# Controller.net
KiCad netlist of a schematic drawn in Altium Designer
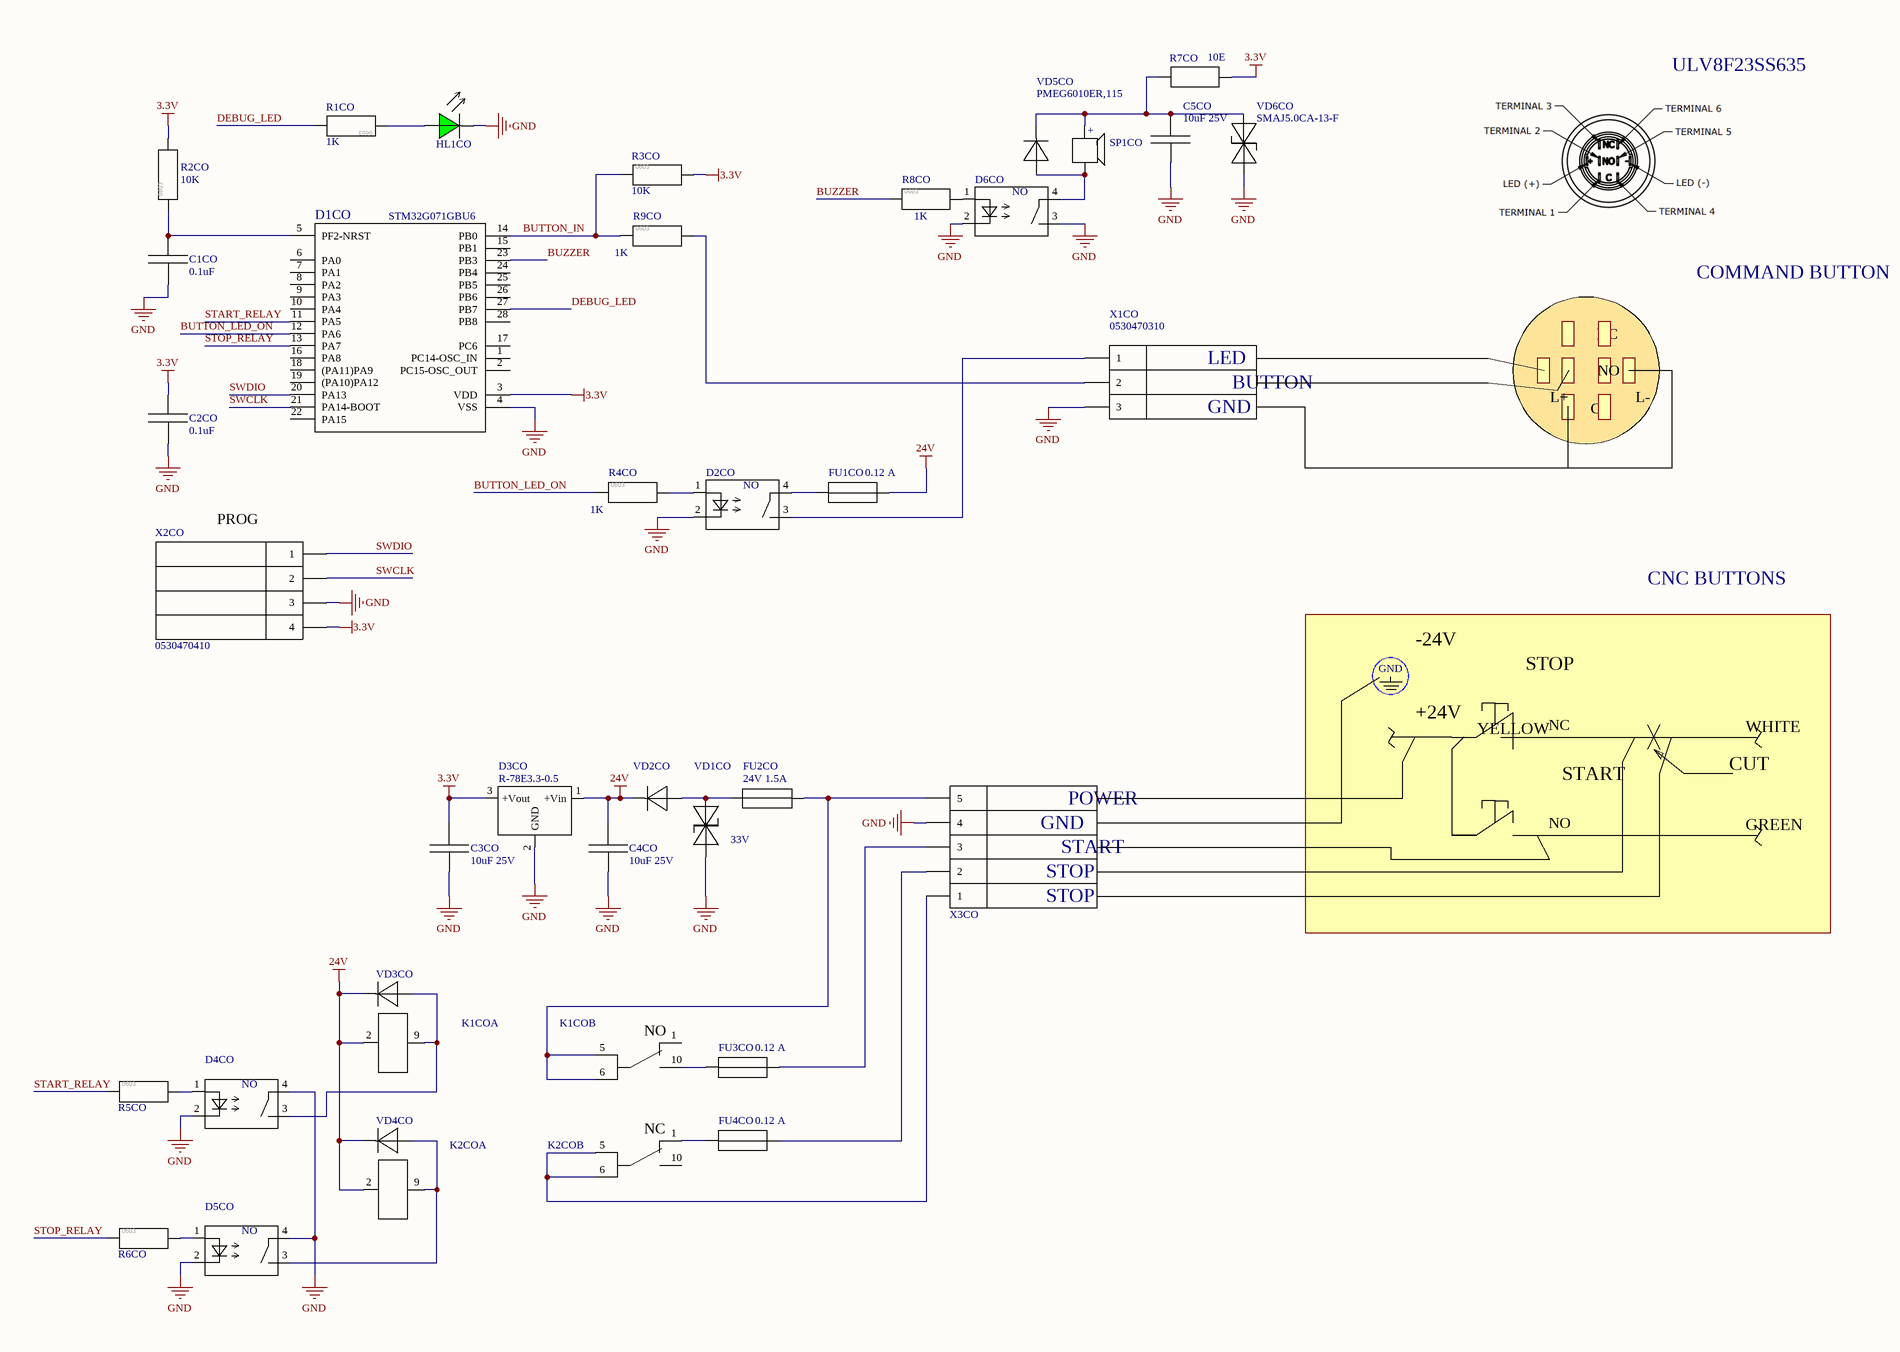
[diagram p0: Controller.SchDoc, left]
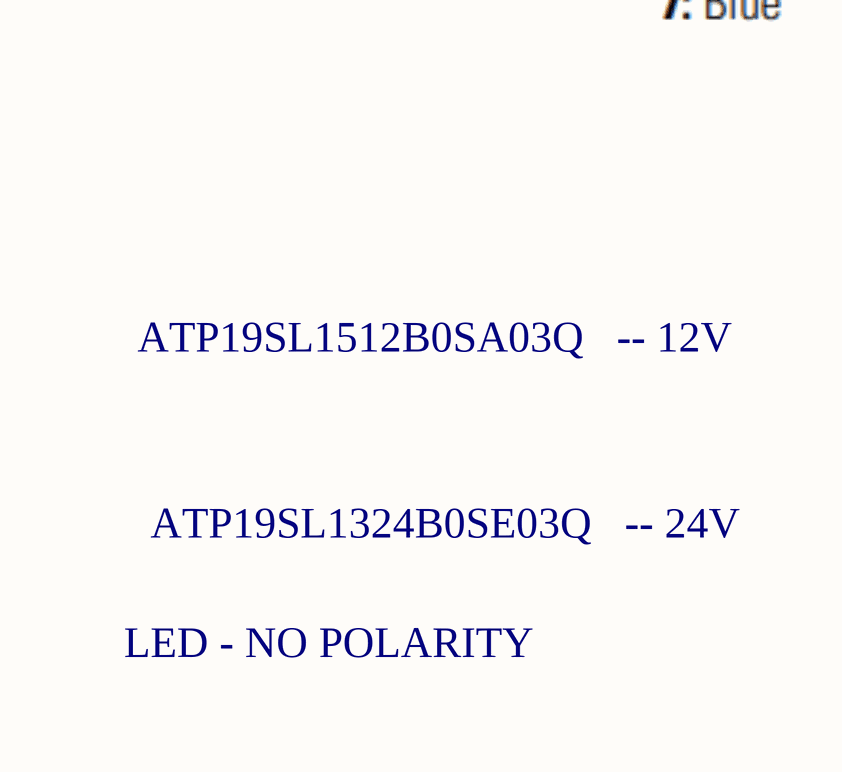
[diagram p1: Controller.SchDoc, right]

(export (version "E")
  (design (tool "Eeschema 10.0.6"))
  (components
    (comp (ref "C1CO")
      (value "0.1uF")
      (footprint "C0603pads")
      (description "CAP CER 0.1UF 50V X7R 0603 jlc")
      (fields
        (field (name "MANUFACTURER") "Samsung Electro-Mechanics")
        (field (name "PART NUMBER") "CL10B104KB8NNNC")
        (field (name "PUBLISHER") "*")
      )
      (libsource (lib "MC2") (part "CL10B104KB8NNNC"))
    )
    (comp (ref "C2CO")
      (value "0.1uF")
      (footprint "C0603pads")
      (description "CAP CER 0.1UF 50V X7R 0603 jlc")
      (fields
        (field (name "MANUFACTURER") "Samsung Electro-Mechanics")
        (field (name "PART NUMBER") "CL10B104KB8NNNC")
        (field (name "PUBLISHER") "*")
      )
      (libsource (lib "MC2") (part "CL10B104KB8NNNC"))
    )
    (comp (ref "C3CO")
      (value "10uF 25V")
      (footprint "C1210 LowESR")
      (description "CAP CER 10UF 25V X8R 1210")
      (fields
        (field (name "PART NUMBER") "C3225X8R1E106K250AC")
        (field (name "MANUFACTURER") "TDK Corporation")
        (field (name "PUBLISHER") "*")
      )
      (libsource (lib "MC2") (part "C3225X8R1E106K250AC"))
    )
    (comp (ref "C4CO")
      (value "10uF 25V")
      (footprint "C1210 LowESR")
      (description "CAP CER 10UF 25V X8R 1210")
      (fields
        (field (name "PART NUMBER") "C3225X8R1E106K250AC")
        (field (name "MANUFACTURER") "TDK Corporation")
        (field (name "PUBLISHER") "*")
      )
      (libsource (lib "MC2") (part "C3225X8R1E106K250AC"))
    )
    (comp (ref "C5CO")
      (value "10uF 25V")
      (footprint "C1210 LowESR")
      (description "CAP CER 10UF 25V X8R 1210")
      (fields
        (field (name "PART NUMBER") "C3225X8R1E106K250AC")
        (field (name "MANUFACTURER") "TDK Corporation")
        (field (name "PUBLISHER") "*")
      )
      (libsource (lib "MC2") (part "C3225X8R1E106K250AC"))
    )
    (comp (ref "D1CO")
      (value "STM32G071GBU6")
      (footprint "UFQFPN28")
      (description "IC MCU 32BIT 128KB FLSH 28UFQFPN jlc")
      (fields (field (name "MANUFACTURER") "STMicroelectronics"))
      (libsource (lib "MC2") (part "STM32G071GBU6"))
    )
    (comp (ref "D2CO")
      (value "CPC1014NTR")
      (footprint "SOP-4")
      (description "SSR RELAY SPST-NO 400MA 0-60V jlc")
      (fields (field (name "MANUFACTURER") "Littelfuse Inc.") (field (name "PUBLISHER") "*"))
      (libsource (lib "MC2") (part "CPC1014NTR"))
    )
    (comp (ref "D3CO")
      (value "R-78E3.3-0.5")
      (footprint "R-78XX-0.5")
      (description "DC DC CONVERTER 3.3V 2W")
      (fields (field (name "MANUFACTURER") "Recom Power"))
      (libsource (lib "MC2") (part "R-78E3.3-0.5"))
    )
    (comp (ref "D4CO")
      (value "CPC1014NTR")
      (footprint "SOP-4")
      (description "SSR RELAY SPST-NO 400MA 0-60V jlc")
      (fields (field (name "MANUFACTURER") "Littelfuse Inc.") (field (name "PUBLISHER") "*"))
      (libsource (lib "MC2") (part "CPC1014NTR"))
    )
    (comp (ref "D5CO")
      (value "CPC1014NTR")
      (footprint "SOP-4")
      (description "SSR RELAY SPST-NO 400MA 0-60V jlc")
      (fields (field (name "MANUFACTURER") "Littelfuse Inc.") (field (name "PUBLISHER") "*"))
      (libsource (lib "MC2") (part "CPC1014NTR"))
    )
    (comp (ref "D6CO")
      (value "CPC1014NTR")
      (footprint "SOP-4")
      (description "SSR RELAY SPST-NO 400MA 0-60V jlc")
      (fields (field (name "MANUFACTURER") "Littelfuse Inc.") (field (name "PUBLISHER") "*"))
      (libsource (lib "MC2") (part "CPC1014NTR"))
    )
    (comp (ref "FU1CO")
      (value "0.12 A")
      (footprint "MC:FUSE 1206")
      (description "PTC RESET FUSE 48V 120MA 1206 jlc")
      (fields
        (field (name "PART NUMBER") "0ZCJ0012FF2E")
        (field (name "MANUFACTURER") "Bel Fuse Inc.")
        (field (name "PUBLISHER") "*")
      )
      (libsource (lib "MC2") (part "0ZCJ0012FF2E"))
    )
    (comp (ref "FU2CO")
      (value "24V 1.5A")
      (footprint "MC2:FUSE 1812")
      (description "PTC RESET FUSE 24V 1.5A 1812 jlc")
      (fields
        (field (name "MANUFACTURER") "Littelfuse Inc.")
        (field (name "PART NUMBER") "1812L150/24MR")
        (field (name "PUBLISHER") "*")
      )
      (libsource (lib "MC2") (part "1812L150/24MR"))
    )
    (comp (ref "FU3CO")
      (value "0.12 A")
      (footprint "MC:FUSE 1206")
      (description "PTC RESET FUSE 48V 120MA 1206 jlc")
      (fields
        (field (name "PART NUMBER") "0ZCJ0012FF2E")
        (field (name "MANUFACTURER") "Bel Fuse Inc.")
        (field (name "PUBLISHER") "*")
      )
      (libsource (lib "MC2") (part "0ZCJ0012FF2E"))
    )
    (comp (ref "FU4CO")
      (value "0.12 A")
      (footprint "MC:FUSE 1206")
      (description "PTC RESET FUSE 48V 120MA 1206 jlc")
      (fields
        (field (name "PART NUMBER") "0ZCJ0012FF2E")
        (field (name "MANUFACTURER") "Bel Fuse Inc.")
        (field (name "PUBLISHER") "*")
      )
      (libsource (lib "MC2") (part "0ZCJ0012FF2E"))
    )
    (comp (ref "HL1CO")
      (value "KT-0805G")
      (footprint "MC2:LED 0805 GREEN")
      (description "LED EMERALD GREEN 0805 SMD jlc")
      (fields (field (name "MANUFACTURER") "Hubei KENTO Elec") (field (name "PUBLISHER") "*"))
      (libsource (lib "MC2") (part "KT-0805G"))
    )
    (comp (ref "K1CO")
      (value "G5V-1-DC24")
      (footprint "MC2:G5V-1")
      (description "RELAY GEN PURPOSE SPDT 1A 24VDC")
      (fields (field (name "MANUFACTURER") "Omron") (field (name "PUBLISHER") "*"))
      (libsource (lib "MC2") (part "G5V-1-DC24"))
    )
    (comp (ref "K2CO")
      (value "G5V-1-DC24")
      (footprint "MC2:G5V-1")
      (description "RELAY GEN PURPOSE SPDT 1A 24VDC")
      (fields (field (name "MANUFACTURER") "Omron") (field (name "PUBLISHER") "*"))
      (libsource (lib "MC2") (part "G5V-1-DC24"))
    )
    (comp (ref "R1CO")
      (value "1K")
      (footprint "R0603_MIN_pads")
      (description "RES SMD 1K OHM 1% 1/10W 0603 jlc")
      (fields
        (field (name "MANUFACTURER") "Yageo")
        (field (name "PART NUMBER") "RC0603FR-071KL")
        (field (name "PUBLISHER") "*")
      )
      (libsource (lib "MC2") (part "RC0603FR-071KL"))
    )
    (comp (ref "R2CO")
      (value "10K")
      (footprint "R0603_pads")
      (description "RES 10K OHM 1% 1/10W 0603 jlc")
      (fields
        (field (name "MANUFACTURER") "Yageo")
        (field (name "PART NUMBER") "RC0603FR-0710KL")
        (field (name "PUBLISHER") "*")
      )
      (libsource (lib "MC2") (part "RC0603FR-0710KL"))
    )
    (comp (ref "R3CO")
      (value "10K")
      (footprint "R0603_pads")
      (description "RES 10K OHM 1% 1/10W 0603 jlc")
      (fields
        (field (name "MANUFACTURER") "Yageo")
        (field (name "PART NUMBER") "RC0603FR-0710KL")
        (field (name "PUBLISHER") "*")
      )
      (libsource (lib "MC2") (part "RC0603FR-0710KL"))
    )
    (comp (ref "R4CO")
      (value "1K")
      (footprint "R0603_MIN_pads")
      (description "RES SMD 1K OHM 1% 1/10W 0603 jlc")
      (fields
        (field (name "MANUFACTURER") "Yageo")
        (field (name "PART NUMBER") "RC0603FR-071KL")
        (field (name "PUBLISHER") "*")
      )
      (libsource (lib "MC2") (part "RC0603FR-071KL"))
    )
    (comp (ref "R5CO")
      (value "RC0603FR-071KL")
      (footprint "R0603_MIN_pads")
      (description "RES SMD 1K OHM 1% 1/10W 0603 jlc")
      (fields (field (name "MANUFACTURER") "Yageo") (field (name "PUBLISHER") "*"))
      (libsource (lib "MC2") (part "RC0603FR-071KL"))
    )
    (comp (ref "R6CO")
      (value "RC0603FR-071KL")
      (footprint "R0603_MIN_pads")
      (description "RES SMD 1K OHM 1% 1/10W 0603 jlc")
      (fields (field (name "MANUFACTURER") "Yageo") (field (name "PUBLISHER") "*"))
      (libsource (lib "MC2") (part "RC0603FR-071KL"))
    )
    (comp (ref "R7CO")
      (value "10E")
      (footprint "MC2:R0805")
      (description "RES 10 OHM 1% 1/8W 0805 jlc")
      (fields
        (field (name "MANUFACTURER") "Yageo")
        (field (name "PART NUMBER") "RC0805FR-0710RL")
        (field (name "PUBLISHER") "*")
      )
      (libsource (lib "MC2") (part "RC0805FR-0710RL"))
    )
    (comp (ref "R8CO")
      (value "1K")
      (footprint "R0603_MIN_pads")
      (description "RES SMD 1K OHM 1% 1/10W 0603 jlc")
      (fields
        (field (name "MANUFACTURER") "Yageo")
        (field (name "PART NUMBER") "RC0603FR-071KL")
        (field (name "PUBLISHER") "*")
      )
      (libsource (lib "MC2") (part "RC0603FR-071KL"))
    )
    (comp (ref "R9CO")
      (value "1K")
      (footprint "R0603_MIN_pads")
      (description "RES SMD 1K OHM 1% 1/10W 0603 jlc")
      (fields
        (field (name "MANUFACTURER") "Yageo")
        (field (name "PART NUMBER") "RC0603FR-071KL")
        (field (name "PUBLISHER") "*")
      )
      (libsource (lib "MC2") (part "RC0603FR-071KL"))
    )
    (comp (ref "SP1CO")
      (value "MLT-9650")
      (footprint "buzer_9.6x9.6")
      (description "85dB Active (Built-in Driver Circuit) Electromagnetic Type 2.7kHz Buzzers ROHS jlc")
      (fields (field (name "MANUFACTURER") "Yageo") (field (name "PUBLISHER") "*"))
      (libsource (lib "MC2") (part "MLT-9650"))
    )
    (comp (ref "VD1CO")
      (value "33V")
      (footprint "MC2:SMAJ")
      (description "TVS DIODE 30VWM 64.3VC SMA")
      (fields
        (field (name "MANUFACTURER") "STMicroelectronics")
        (field (name "PART NUMBER") "SMAJ30CA-TR")
        (field (name "PUBLISHER") "*")
      )
      (libsource (lib "MC2") (part "SMAJ30CA-TR"))
    )
    (comp (ref "VD2CO")
      (value "PMEG6010ER,115")
      (footprint "SOD123")
      (description "DIODE SCHOTTKY 60V 1A SOD123W")
      (fields (field (name "MANUFACTURER") "Nexperia USA Inc.") (field (name "PUBLISHER") "*"))
      (libsource (lib "MC2") (part "PMEG6010ER,115"))
    )
    (comp (ref "VD3CO")
      (value "PMEG6010ER,115")
      (footprint "SOD123")
      (description "DIODE SCHOTTKY 60V 1A SOD123W")
      (fields (field (name "MANUFACTURER") "Nexperia USA Inc.") (field (name "PUBLISHER") "*"))
      (libsource (lib "MC2") (part "PMEG6010ER,115"))
    )
    (comp (ref "VD4CO")
      (value "PMEG6010ER,115")
      (footprint "SOD123")
      (description "DIODE SCHOTTKY 60V 1A SOD123W")
      (fields (field (name "MANUFACTURER") "Nexperia USA Inc.") (field (name "PUBLISHER") "*"))
      (libsource (lib "MC2") (part "PMEG6010ER,115"))
    )
    (comp (ref "VD5CO")
      (value "PMEG6010ER,115")
      (footprint "SOD123")
      (description "DIODE SCHOTTKY 60V 1A SOD123W")
      (fields
        (field (name "MANUFACTURER") "Nexperia USA Inc.")
        (field (name "PART NUMBER") "PMEG6010ER,115")
        (field (name "PUBLISHER") "*")
      )
      (libsource (lib "MC2") (part "PMEG6010ER,115"))
    )
    (comp (ref "VD6CO")
      (value "SMAJ5.0CA-13-F")
      (footprint "MC2:SMAJ")
      (description "TVS DIODE 5VWM 9.2VC SMA jlc")
      (fields (field (name "MANUFACTURER") "Diodes Incorporated") (field (name "PUBLISHER") "*"))
      (libsource (lib "MC2") (part "SMAJ5.0CA-13-F"))
    )
    (comp (ref "X1CO")
      (value "0530470310")
      (footprint "0530470310")
      (description "CONN HEADER VERT 3POS 1.25MM jlc")
      (fields (field (name "MANUFACTURER") "Molex") (field (name "PUBLISHER") "*"))
      (libsource (lib "MC2") (part "0530470310"))
    )
    (comp (ref "X2CO")
      (value "0530470410")
      (footprint "0530470410")
      (description "CONN HEADER VERT 4POS 1.25MM")
      (fields (field (name "MANUFACTURER") "Molex") (field (name "PUBLISHER") "*"))
      (libsource (lib "MC2") (part "0530470410"))
    )
    (comp (ref "X3CO")
      (value "1984992")
      (footprint "1984992")
      (description "TERM BLOCK 5POS 45DEG 3.5MM PCB")
      (fields (field (name "MANUFACTURER") "Phoenix Contact") (field (name "PUBLISHER") "*"))
      (libsource (lib "MC2") (part "1984992"))
    )
  )
  (nets
    (net (code "1") (name "/BUTTON_IN") (class "Default")
      (node (ref "D1CO") (pin "14") (pinfunction "PB0_14") (pintype "passive"))
      (node (ref "R3CO") (pin "1") (pinfunction "1_1") (pintype "passive"))
      (node (ref "R9CO") (pin "1") (pinfunction "1_1") (pintype "passive"))
    )
    (net (code "2") (name "/BUTTON_LED_ON") (class "Default")
      (node (ref "D1CO") (pin "12") (pinfunction "PA6_12") (pintype "passive"))
      (node (ref "R4CO") (pin "1") (pinfunction "1_1") (pintype "passive"))
    )
    (net (code "3") (name "/BUZZER") (class "Default")
      (node (ref "D1CO") (pin "23") (pinfunction "PB3_23") (pintype "passive"))
      (node (ref "R8CO") (pin "1") (pinfunction "1_1") (pintype "passive"))
    )
    (net (code "4") (name "/DEBUG_LED") (class "Default")
      (node (ref "D1CO") (pin "27") (pinfunction "PB7_27") (pintype "passive"))
      (node (ref "R1CO") (pin "2") (pinfunction "2_2") (pintype "passive"))
    )
    (net (code "5") (name "/START_RELAY") (class "Default")
      (node (ref "D1CO") (pin "11") (pinfunction "PA5_11") (pintype "passive"))
      (node (ref "R5CO") (pin "1") (pinfunction "1_1") (pintype "passive"))
    )
    (net (code "6") (name "/STOP_RELAY") (class "Default")
      (node (ref "D1CO") (pin "13") (pinfunction "PA7_13") (pintype "passive"))
      (node (ref "R6CO") (pin "1") (pinfunction "1_1") (pintype "passive"))
    )
    (net (code "7") (name "/SWCLK") (class "Default")
      (node (ref "D1CO") (pin "21") (pinfunction "PA14-BOOT_21") (pintype "passive"))
      (node (ref "X2CO") (pin "2") (pinfunction "2_2") (pintype "passive"))
    )
    (net (code "8") (name "/SWDIO") (class "Default")
      (node (ref "D1CO") (pin "20") (pinfunction "PA13_20") (pintype "passive"))
      (node (ref "X2CO") (pin "1") (pinfunction "1_1") (pintype "passive"))
    )
    (net (code "9") (name "3.3V") (class "Default")
      (node (ref "C2CO") (pin "1") (pinfunction "1_1") (pintype "passive"))
      (node (ref "C3CO") (pin "2") (pinfunction "2_2") (pintype "passive"))
      (node (ref "D1CO") (pin "3") (pinfunction "VDD_3") (pintype "power_in"))
      (node (ref "D3CO") (pin "3") (pinfunction "+Vout_3") (pintype "passive"))
      (node (ref "R2CO") (pin "2") (pinfunction "2_2") (pintype "passive"))
      (node (ref "R3CO") (pin "2") (pinfunction "2_2") (pintype "passive"))
      (node (ref "R7CO") (pin "2") (pinfunction "2_2") (pintype "passive"))
      (node (ref "X2CO") (pin "4") (pinfunction "4_4") (pintype "passive"))
    )
    (net (code "10") (name "24V") (class "Default")
      (node (ref "C4CO") (pin "2") (pinfunction "2_2") (pintype "passive"))
      (node (ref "D3CO") (pin "1") (pinfunction "+Vin_1") (pintype "passive"))
      (node (ref "FU1CO") (pin "2") (pinfunction "2_2") (pintype "passive"))
      (node (ref "K1CO") (pin "2") (pinfunction "2_2") (pintype "passive"))
      (node (ref "K2CO") (pin "2") (pinfunction "2_2") (pintype "passive"))
      (node (ref "VD2CO") (pin "1") (pinfunction "1_1") (pintype "passive"))
      (node (ref "VD3CO") (pin "1") (pinfunction "1_1") (pintype "passive"))
      (node (ref "VD4CO") (pin "1") (pinfunction "1_1") (pintype "passive"))
    )
    (net (code "11") (name "GND") (class "Default")
      (node (ref "C1CO") (pin "2") (pinfunction "2_2") (pintype "passive"))
      (node (ref "C2CO") (pin "2") (pinfunction "2_2") (pintype "passive"))
      (node (ref "C3CO") (pin "1") (pinfunction "1_1") (pintype "passive"))
      (node (ref "C4CO") (pin "1") (pinfunction "1_1") (pintype "passive"))
      (node (ref "C5CO") (pin "1") (pinfunction "1_1") (pintype "passive"))
      (node (ref "D1CO") (pin "4") (pinfunction "VSS_4") (pintype "power_in"))
      (node (ref "D2CO") (pin "2") (pinfunction "2_2") (pintype "passive"))
      (node (ref "D3CO") (pin "2") (pinfunction "GND_2") (pintype "passive"))
      (node (ref "D4CO") (pin "2") (pinfunction "2_2") (pintype "passive"))
      (node (ref "D4CO") (pin "4") (pinfunction "4_4") (pintype "passive"))
      (node (ref "D5CO") (pin "2") (pinfunction "2_2") (pintype "passive"))
      (node (ref "D5CO") (pin "4") (pinfunction "4_4") (pintype "passive"))
      (node (ref "D6CO") (pin "2") (pinfunction "2_2") (pintype "passive"))
      (node (ref "D6CO") (pin "3") (pinfunction "3_3") (pintype "passive"))
      (node (ref "HL1CO") (pin "2") (pinfunction "2_2") (pintype "passive"))
      (node (ref "VD1CO") (pin "1") (pinfunction "1_1") (pintype "passive"))
      (node (ref "VD6CO") (pin "1") (pinfunction "1_1") (pintype "passive"))
      (node (ref "X1CO") (pin "3") (pinfunction "3_3") (pintype "passive"))
      (node (ref "X2CO") (pin "3") (pinfunction "3_3") (pintype "passive"))
      (node (ref "X3CO") (pin "4") (pinfunction "4_4") (pintype "passive"))
    )
    (net (code "12") (name "Net-(C5CO-Pad2)") (class "Default")
      (node (ref "C5CO") (pin "2") (pinfunction "2_2") (pintype "passive"))
      (node (ref "R7CO") (pin "1") (pinfunction "1_1") (pintype "passive"))
      (node (ref "SP1CO") (pin "1") (pinfunction "1_1") (pintype "passive"))
      (node (ref "VD5CO") (pin "1") (pinfunction "1_1") (pintype "passive"))
      (node (ref "VD6CO") (pin "2") (pinfunction "2_2") (pintype "passive"))
    )
    (net (code "13") (name "Net-(D1CO-PF2-NRST)") (class "Default")
      (node (ref "C1CO") (pin "1") (pinfunction "1_1") (pintype "passive"))
      (node (ref "D1CO") (pin "5") (pinfunction "PF2-NRST_5") (pintype "passive"))
      (node (ref "R2CO") (pin "1") (pinfunction "1_1") (pintype "passive"))
    )
    (net (code "14") (name "Net-(D2CO-Pad1)") (class "Default")
      (node (ref "D2CO") (pin "1") (pinfunction "1_1") (pintype "passive"))
      (node (ref "R4CO") (pin "2") (pinfunction "2_2") (pintype "passive"))
    )
    (net (code "15") (name "Net-(D2CO-Pad3)") (class "Default")
      (node (ref "D2CO") (pin "3") (pinfunction "3_3") (pintype "passive"))
      (node (ref "X1CO") (pin "1") (pinfunction "1_1") (pintype "passive"))
    )
    (net (code "16") (name "Net-(D2CO-Pad4)") (class "Default")
      (node (ref "D2CO") (pin "4") (pinfunction "4_4") (pintype "passive"))
      (node (ref "FU1CO") (pin "1") (pinfunction "1_1") (pintype "passive"))
    )
    (net (code "17") (name "Net-(D4CO-Pad1)") (class "Default")
      (node (ref "D4CO") (pin "1") (pinfunction "1_1") (pintype "passive"))
      (node (ref "R5CO") (pin "2") (pinfunction "2_2") (pintype "passive"))
    )
    (net (code "18") (name "Net-(D4CO-Pad3)") (class "Default")
      (node (ref "D4CO") (pin "3") (pinfunction "3_3") (pintype "passive"))
      (node (ref "K1CO") (pin "9") (pinfunction "9_9") (pintype "passive"))
      (node (ref "VD3CO") (pin "2") (pinfunction "2_2") (pintype "passive"))
    )
    (net (code "19") (name "Net-(D5CO-Pad1)") (class "Default")
      (node (ref "D5CO") (pin "1") (pinfunction "1_1") (pintype "passive"))
      (node (ref "R6CO") (pin "2") (pinfunction "2_2") (pintype "passive"))
    )
    (net (code "20") (name "Net-(D5CO-Pad3)") (class "Default")
      (node (ref "D5CO") (pin "3") (pinfunction "3_3") (pintype "passive"))
      (node (ref "K2CO") (pin "9") (pinfunction "9_9") (pintype "passive"))
      (node (ref "VD4CO") (pin "2") (pinfunction "2_2") (pintype "passive"))
    )
    (net (code "21") (name "Net-(D6CO-Pad1)") (class "Default")
      (node (ref "D6CO") (pin "1") (pinfunction "1_1") (pintype "passive"))
      (node (ref "R8CO") (pin "2") (pinfunction "2_2") (pintype "passive"))
    )
    (net (code "22") (name "Net-(D6CO-Pad4)") (class "Default")
      (node (ref "D6CO") (pin "4") (pinfunction "4_4") (pintype "passive"))
      (node (ref "SP1CO") (pin "2") (pinfunction "2_2") (pintype "passive"))
      (node (ref "VD5CO") (pin "2") (pinfunction "2_2") (pintype "passive"))
    )
    (net (code "23") (name "Net-(FU2CO-Pad1)") (class "Default")
      (node (ref "FU2CO") (pin "1") (pinfunction "1_1") (pintype "passive"))
      (node (ref "K1CO") (pin "5") (pinfunction "5_5") (pintype "passive"))
      (node (ref "K1CO") (pin "6") (pinfunction "6_6") (pintype "passive"))
      (node (ref "X3CO") (pin "5") (pinfunction "5_5") (pintype "passive"))
    )
    (net (code "24") (name "Net-(FU2CO-Pad2)") (class "Default")
      (node (ref "FU2CO") (pin "2") (pinfunction "2_2") (pintype "passive"))
      (node (ref "VD1CO") (pin "2") (pinfunction "2_2") (pintype "passive"))
      (node (ref "VD2CO") (pin "2") (pinfunction "2_2") (pintype "passive"))
    )
    (net (code "25") (name "Net-(FU3CO-Pad1)") (class "Default")
      (node (ref "FU3CO") (pin "1") (pinfunction "1_1") (pintype "passive"))
      (node (ref "K1CO") (pin "10") (pinfunction "10_10") (pintype "passive"))
    )
    (net (code "26") (name "Net-(FU3CO-Pad2)") (class "Default")
      (node (ref "FU3CO") (pin "2") (pinfunction "2_2") (pintype "passive"))
      (node (ref "X3CO") (pin "3") (pinfunction "3_3") (pintype "passive"))
    )
    (net (code "27") (name "Net-(FU4CO-Pad1)") (class "Default")
      (node (ref "FU4CO") (pin "1") (pinfunction "1_1") (pintype "passive"))
      (node (ref "K2CO") (pin "1") (pinfunction "1_1") (pintype "passive"))
    )
    (net (code "28") (name "Net-(FU4CO-Pad2)") (class "Default")
      (node (ref "FU4CO") (pin "2") (pinfunction "2_2") (pintype "passive"))
      (node (ref "X3CO") (pin "2") (pinfunction "2_2") (pintype "passive"))
    )
    (net (code "29") (name "Net-(HL1CO-Pad1)") (class "Default")
      (node (ref "HL1CO") (pin "1") (pinfunction "1_1") (pintype "passive"))
      (node (ref "R1CO") (pin "1") (pinfunction "1_1") (pintype "passive"))
    )
    (net (code "30") (name "Net-(K2CO-Pad5)") (class "Default")
      (node (ref "K2CO") (pin "5") (pinfunction "5_5") (pintype "passive"))
      (node (ref "K2CO") (pin "6") (pinfunction "6_6") (pintype "passive"))
      (node (ref "X3CO") (pin "1") (pinfunction "1_1") (pintype "passive"))
    )
    (net (code "31") (name "Net-(R9CO-Pad2)") (class "Default")
      (node (ref "R9CO") (pin "2") (pinfunction "2_2") (pintype "passive"))
      (node (ref "X1CO") (pin "2") (pinfunction "2_2") (pintype "passive"))
    )
    (net (code "32") (name "unconnected-(D1CO-(PA10)PA12-Pad19)") (class "Default")
      (node (ref "D1CO") (pin "19") (pinfunction "(PA10)PA12_19") (pintype "passive"))
    )
    (net (code "33") (name "unconnected-(D1CO-(PA11)PA9-Pad18)") (class "Default")
      (node (ref "D1CO") (pin "18") (pinfunction "(PA11)PA9_18") (pintype "passive"))
    )
    (net (code "34") (name "unconnected-(D1CO-PA0-Pad6)") (class "Default")
      (node (ref "D1CO") (pin "6") (pinfunction "PA0_6") (pintype "passive"))
    )
    (net (code "35") (name "unconnected-(D1CO-PA1-Pad7)") (class "Default")
      (node (ref "D1CO") (pin "7") (pinfunction "PA1_7") (pintype "passive"))
    )
    (net (code "36") (name "unconnected-(D1CO-PA2-Pad8)") (class "Default")
      (node (ref "D1CO") (pin "8") (pinfunction "PA2_8") (pintype "passive"))
    )
    (net (code "37") (name "unconnected-(D1CO-PA3-Pad9)") (class "Default")
      (node (ref "D1CO") (pin "9") (pinfunction "PA3_9") (pintype "passive"))
    )
    (net (code "38") (name "unconnected-(D1CO-PA4-Pad10)") (class "Default")
      (node (ref "D1CO") (pin "10") (pinfunction "PA4_10") (pintype "passive"))
    )
    (net (code "39") (name "unconnected-(D1CO-PA8-Pad16)") (class "Default")
      (node (ref "D1CO") (pin "16") (pinfunction "PA8_16") (pintype "passive"))
    )
    (net (code "40") (name "unconnected-(D1CO-PA15-Pad22)") (class "Default")
      (node (ref "D1CO") (pin "22") (pinfunction "PA15_22") (pintype "passive"))
    )
    (net (code "41") (name "unconnected-(D1CO-PB1-Pad15)") (class "Default")
      (node (ref "D1CO") (pin "15") (pinfunction "PB1_15") (pintype "passive"))
    )
    (net (code "42") (name "unconnected-(D1CO-PB4-Pad24)") (class "Default")
      (node (ref "D1CO") (pin "24") (pinfunction "PB4_24") (pintype "passive"))
    )
    (net (code "43") (name "unconnected-(D1CO-PB5-Pad25)") (class "Default")
      (node (ref "D1CO") (pin "25") (pinfunction "PB5_25") (pintype "passive"))
    )
    (net (code "44") (name "unconnected-(D1CO-PB6-Pad26)") (class "Default")
      (node (ref "D1CO") (pin "26") (pinfunction "PB6_26") (pintype "passive"))
    )
    (net (code "45") (name "unconnected-(D1CO-PB8-Pad28)") (class "Default")
      (node (ref "D1CO") (pin "28") (pinfunction "PB8_28") (pintype "passive"))
    )
    (net (code "46") (name "unconnected-(D1CO-PC6-Pad17)") (class "Default")
      (node (ref "D1CO") (pin "17") (pinfunction "PC6_17") (pintype "passive"))
    )
    (net (code "47") (name "unconnected-(D1CO-PC14-OSC_IN-Pad1)") (class "Default")
      (node (ref "D1CO") (pin "1") (pinfunction "PC14-OSC_IN_1") (pintype "passive"))
    )
    (net (code "48") (name "unconnected-(D1CO-PC15-OSC_OUT-Pad2)") (class "Default")
      (node (ref "D1CO") (pin "2") (pinfunction "PC15-OSC_OUT_2") (pintype "passive"))
    )
    (net (code "49") (name "unconnected-(K1CO-Pad1)") (class "Default")
      (node (ref "K1CO") (pin "1") (pinfunction "1_1") (pintype "passive"))
    )
    (net (code "50") (name "unconnected-(K2CO-Pad10)") (class "Default")
      (node (ref "K2CO") (pin "10") (pinfunction "10_10") (pintype "passive"))
    )
  )
)
